# Mixer-Analog-OPA2134-Rev-K2.net
KiCad netlist of a schematic drawn in EAGLE
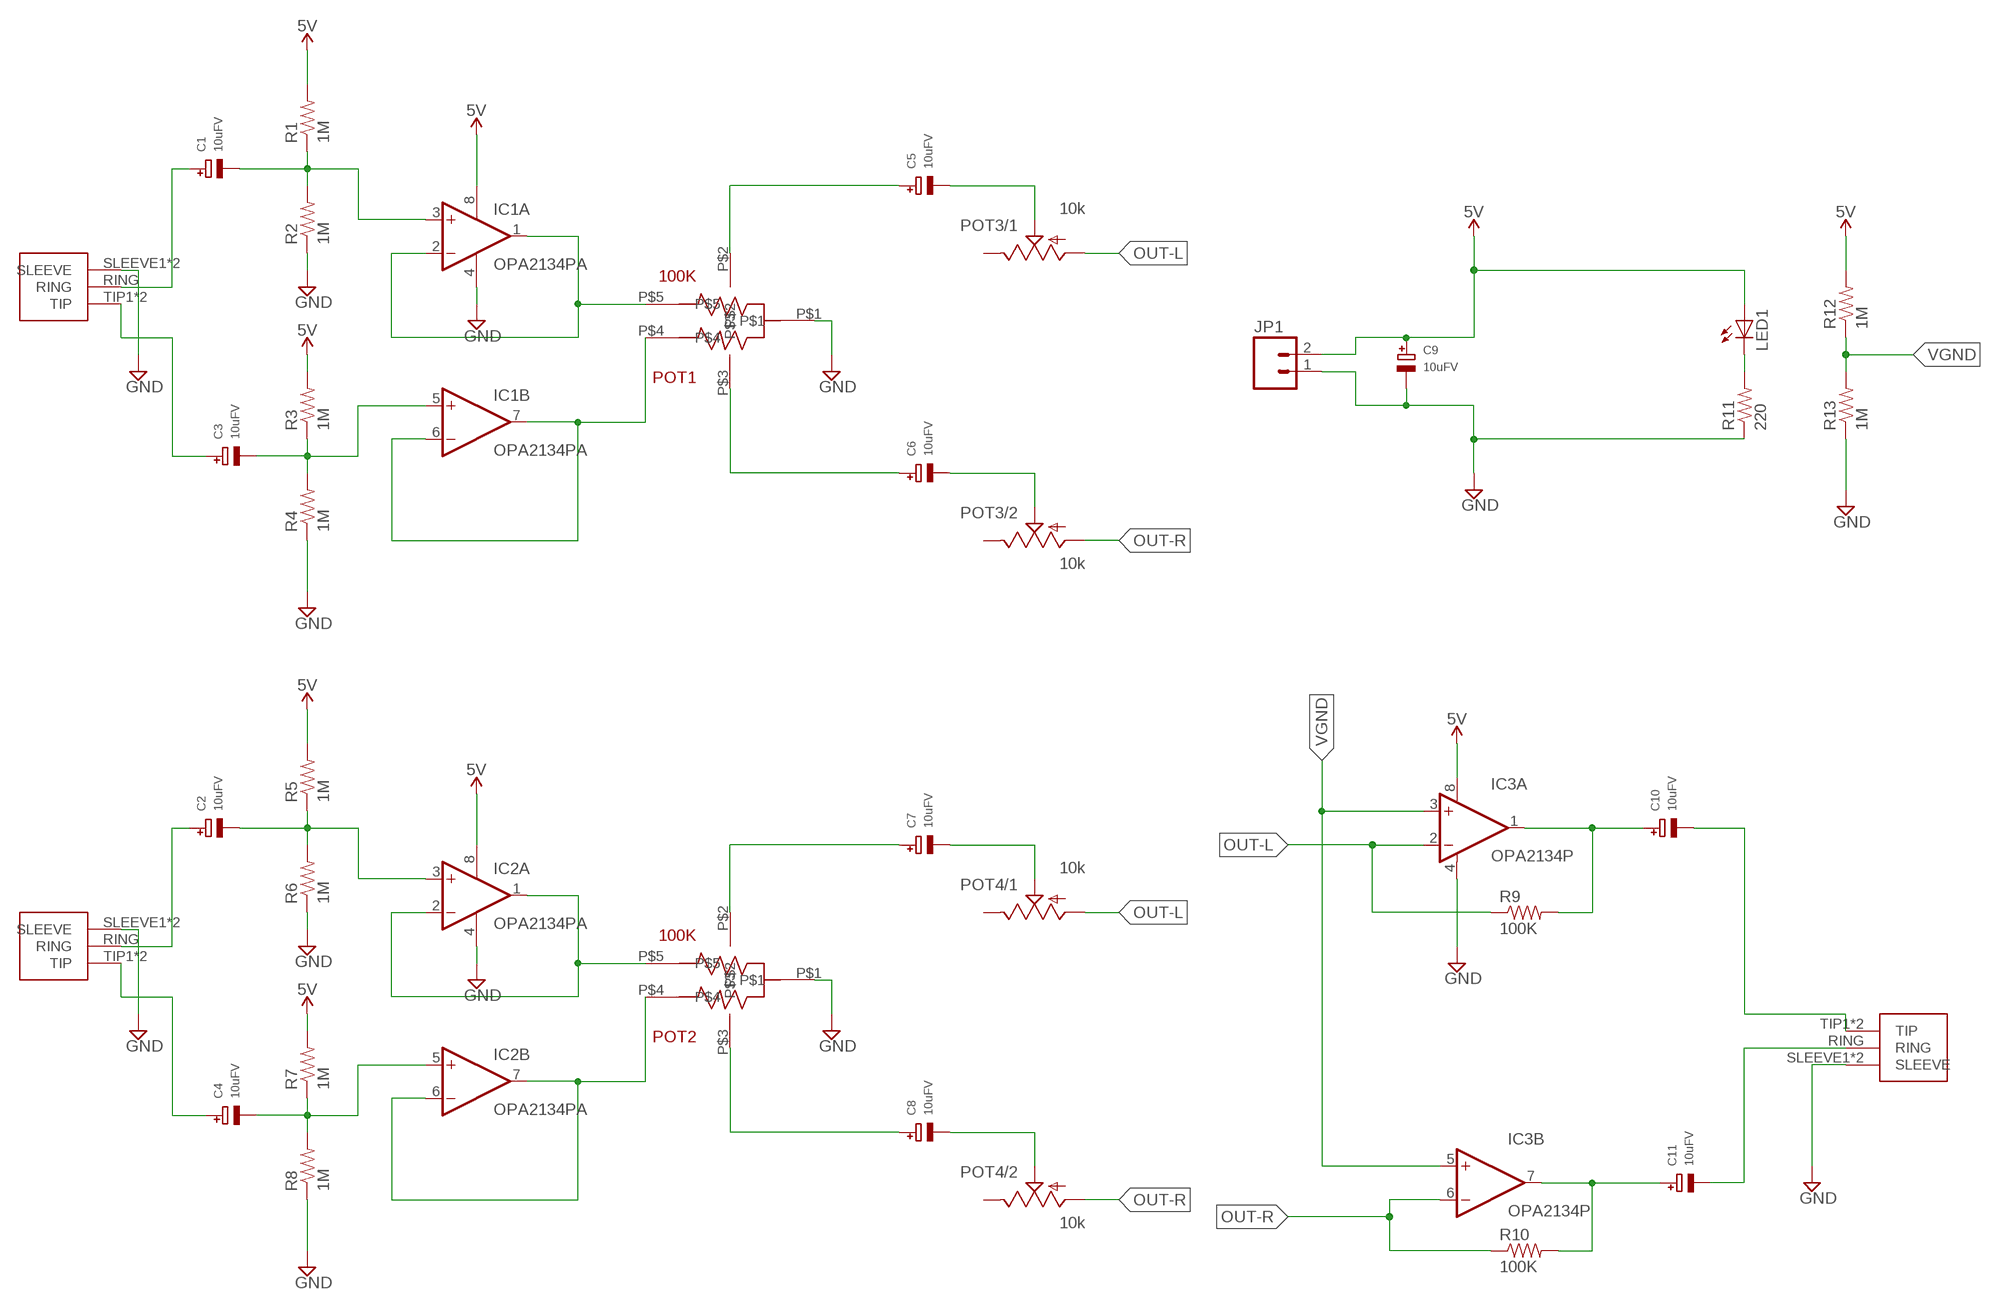
[diagram p0: schematic, sheet 1]

(export (version "E")
  (design (tool "Eeschema 10.0.6"))
  (components
    (comp (ref "C1")
      (value "10uFV")
      (footprint "eagle-import:CELEC_3.5MM_8MM")
      (libsource (lib "eagle-import") (part "CAP_ELECTROLYTICPTH_3.5MMGRID_8MMDIA"))
    )
    (comp (ref "C2")
      (value "10uFV")
      (footprint "eagle-import:CELEC_3.5MM_8MM")
      (libsource (lib "eagle-import") (part "CAP_ELECTROLYTICPTH_3.5MMGRID_8MMDIA"))
    )
    (comp (ref "C3")
      (value "10uFV")
      (footprint "eagle-import:CELEC_3.5MM_8MM")
      (libsource (lib "eagle-import") (part "CAP_ELECTROLYTICPTH_3.5MMGRID_8MMDIA"))
    )
    (comp (ref "C4")
      (value "10uFV")
      (footprint "eagle-import:CELEC_3.5MM_8MM")
      (libsource (lib "eagle-import") (part "CAP_ELECTROLYTICPTH_3.5MMGRID_8MMDIA"))
    )
    (comp (ref "C5")
      (value "10uFV")
      (footprint "eagle-import:CELEC_3.5MM_8MM")
      (libsource (lib "eagle-import") (part "CAP_ELECTROLYTICPTH_3.5MMGRID_8MMDIA"))
    )
    (comp (ref "C6")
      (value "10uFV")
      (footprint "eagle-import:CELEC_3.5MM_8MM")
      (libsource (lib "eagle-import") (part "CAP_ELECTROLYTICPTH_3.5MMGRID_8MMDIA"))
    )
    (comp (ref "C7")
      (value "10uFV")
      (footprint "eagle-import:CELEC_3.5MM_8MM")
      (libsource (lib "eagle-import") (part "CAP_ELECTROLYTICPTH_3.5MMGRID_8MMDIA"))
    )
    (comp (ref "C8")
      (value "10uFV")
      (footprint "eagle-import:CELEC_3.5MM_8MM")
      (libsource (lib "eagle-import") (part "CAP_ELECTROLYTICPTH_3.5MMGRID_8MMDIA"))
    )
    (comp (ref "C9")
      (value "10uFV")
      (footprint "eagle-import:CELEC_3.5MM_8MM")
      (libsource (lib "eagle-import") (part "CAP_ELECTROLYTICPTH_3.5MMGRID_8MMDIA"))
    )
    (comp (ref "C10")
      (value "10uFV")
      (footprint "eagle-import:CELEC_3.5MM_8MM")
      (libsource (lib "eagle-import") (part "CAP_ELECTROLYTICPTH_3.5MMGRID_8MMDIA"))
    )
    (comp (ref "C11")
      (value "10uFV")
      (footprint "eagle-import:CELEC_3.5MM_8MM")
      (libsource (lib "eagle-import") (part "CAP_ELECTROLYTICPTH_3.5MMGRID_8MMDIA"))
    )
    (comp (ref "IC1")
      (value "OPA2134PA")
      (footprint "eagle-import:DIL08")
      (libsource (lib "eagle-import") (part "OPA2PA134"))
    )
    (comp (ref "IC2")
      (value "OPA2134PA")
      (footprint "eagle-import:DIL08")
      (libsource (lib "eagle-import") (part "OPA2PA134"))
    )
    (comp (ref "IC3")
      (value "OPA2134P")
      (footprint "eagle-import:DIL08")
      (fields (field (name "MF") "TEXAS INSTRUMENTS") (field (name "MPN") "OPA2134PA"))
      (libsource (lib "eagle-import") (part "OPA2134P"))
    )
    (comp (ref "J1")
      (value "1/8\"-F-STEREO-PCB")
      (footprint "eagle-import:1_8_-F-STEREO-PCB")
      (libsource (lib "eagle-import") (part "1/8{dblquote}-F-STEREO-PCB"))
    )
    (comp (ref "J2")
      (value "1/8\"-F-STEREO-PCB")
      (footprint "eagle-import:1_8_-F-STEREO-PCB")
      (libsource (lib "eagle-import") (part "1/8{dblquote}-F-STEREO-PCB"))
    )
    (comp (ref "J3")
      (value "1/8\"-F-STEREO-PCB")
      (footprint "eagle-import:1_8_-F-STEREO-PCB")
      (libsource (lib "eagle-import") (part "1/8{dblquote}-F-STEREO-PCB"))
    )
    (comp (ref "JP1")
      (value "M02LOCK")
      (footprint "eagle-import:1X02_LOCK")
      (libsource (lib "eagle-import") (part "M02LOCK"))
    )
    (comp (ref "LED1")
      (value "LED3MM")
      (footprint "eagle-import:LED3MM")
      (libsource (lib "eagle-import") (part "LED3MM"))
    )
    (comp (ref "POT1")
      (value "100K")
      (footprint "eagle-import:POT-DUAL-ALPS-RK10J12E0A0A")
      (libsource (lib "eagle-import") (part "POT-DUAL-ALPS-RK10J12E0A0A"))
    )
    (comp (ref "POT2")
      (value "100K")
      (footprint "eagle-import:POT-DUAL-ALPS-RK10J12E0A0A")
      (libsource (lib "eagle-import") (part "POT-DUAL-ALPS-RK10J12E0A0A"))
    )
    (comp (ref "POT3")
      (value "10k")
      (footprint "eagle-import:PTV112")
      (fields
        (field (name "MF") "STMicroelectronics")
        (field (name "MP") "PTV112")
        (field (name "SPICEPREFIX") "J")
      )
      (libsource (lib "eagle-import") (part "POT-DUAL-PTV112-4420"))
    )
    (comp (ref "POT4")
      (value "10k")
      (footprint "eagle-import:PTV112")
      (fields
        (field (name "MF") "STMicroelectronics")
        (field (name "MP") "PTV112")
        (field (name "SPICEPREFIX") "J")
      )
      (libsource (lib "eagle-import") (part "POT-DUAL-PTV112-4420"))
    )
    (comp (ref "R1")
      (value "1M")
      (footprint "eagle-import:AXIAL-0.3EZ")
      (fields (field (name "SPICEPREFIX") "R"))
      (libsource (lib "eagle-import") (part "RESISTOREZ"))
    )
    (comp (ref "R2")
      (value "1M")
      (footprint "eagle-import:AXIAL-0.3")
      (fields (field (name "SPICEPREFIX") "R"))
      (libsource (lib "eagle-import") (part "RESISTORAXIAL-0.3"))
    )
    (comp (ref "R3")
      (value "1M")
      (footprint "eagle-import:AXIAL-0.3EZ")
      (fields (field (name "SPICEPREFIX") "R"))
      (libsource (lib "eagle-import") (part "RESISTOREZ"))
    )
    (comp (ref "R4")
      (value "1M")
      (footprint "eagle-import:AXIAL-0.3EZ")
      (fields (field (name "SPICEPREFIX") "R"))
      (libsource (lib "eagle-import") (part "RESISTOREZ"))
    )
    (comp (ref "R5")
      (value "1M")
      (footprint "eagle-import:AXIAL-0.3EZ")
      (fields (field (name "SPICEPREFIX") "R"))
      (libsource (lib "eagle-import") (part "RESISTOREZ"))
    )
    (comp (ref "R6")
      (value "1M")
      (footprint "eagle-import:AXIAL-0.3")
      (fields (field (name "SPICEPREFIX") "R"))
      (libsource (lib "eagle-import") (part "RESISTORAXIAL-0.3"))
    )
    (comp (ref "R7")
      (value "1M")
      (footprint "eagle-import:AXIAL-0.3EZ")
      (fields (field (name "SPICEPREFIX") "R"))
      (libsource (lib "eagle-import") (part "RESISTOREZ"))
    )
    (comp (ref "R8")
      (value "1M")
      (footprint "eagle-import:AXIAL-0.3EZ")
      (fields (field (name "SPICEPREFIX") "R"))
      (libsource (lib "eagle-import") (part "RESISTOREZ"))
    )
    (comp (ref "R9")
      (value "100K")
      (footprint "eagle-import:AXIAL-0.3EZ")
      (fields (field (name "SPICEPREFIX") "R"))
      (libsource (lib "eagle-import") (part "RESISTOREZ"))
    )
    (comp (ref "R10")
      (value "100K")
      (footprint "eagle-import:AXIAL-0.3EZ")
      (fields (field (name "SPICEPREFIX") "R"))
      (libsource (lib "eagle-import") (part "RESISTOREZ"))
    )
    (comp (ref "R11")
      (value "220")
      (footprint "eagle-import:AXIAL-0.3EZ")
      (libsource (lib "eagle-import") (part "RESISTOREZ"))
    )
    (comp (ref "R12")
      (value "1M")
      (footprint "eagle-import:AXIAL-0.3EZ")
      (libsource (lib "eagle-import") (part "RESISTOREZ"))
    )
    (comp (ref "R13")
      (value "1M")
      (footprint "eagle-import:AXIAL-0.3EZ")
      (libsource (lib "eagle-import") (part "RESISTOREZ"))
    )
  )
  (nets
    (net (code "1") (name "5V") (class "Default")
      (node (ref "C9") (pin "+") (pinfunction "+_+") (pintype "passive"))
      (node (ref "IC1") (pin "8") (pinfunction "V+_8") (pintype "power_in"))
      (node (ref "IC2") (pin "8") (pinfunction "V+_8") (pintype "power_in"))
      (node (ref "IC3") (pin "8") (pinfunction "V+_8") (pintype "power_in"))
      (node (ref "JP1") (pin "2") (pinfunction "2_2") (pintype "passive"))
      (node (ref "LED1") (pin "A") (pinfunction "A_A") (pintype "passive"))
      (node (ref "R1") (pin "P$2") (pinfunction "2_P$2") (pintype "passive"))
      (node (ref "R12") (pin "P$2") (pinfunction "2_P$2") (pintype "passive"))
      (node (ref "R3") (pin "P$2") (pinfunction "2_P$2") (pintype "passive"))
      (node (ref "R5") (pin "P$2") (pinfunction "2_P$2") (pintype "passive"))
      (node (ref "R7") (pin "P$2") (pinfunction "2_P$2") (pintype "passive"))
    )
    (net (code "2") (name "GND") (class "Default")
      (node (ref "C9") (pin "-") (pinfunction "-_-") (pintype "passive"))
      (node (ref "IC1") (pin "4") (pinfunction "V-_4") (pintype "power_in"))
      (node (ref "IC2") (pin "4") (pinfunction "V-_4") (pintype "power_in"))
      (node (ref "IC3") (pin "4") (pinfunction "V-_4") (pintype "power_in"))
      (node (ref "J1") (pin "SLEEVE1") (pinfunction "SLEEVE_SLEEVE1") (pintype "bidirectional"))
      (node (ref "J1") (pin "SLEEVE2") (pinfunction "SLEEVE_SLEEVE2") (pintype "bidirectional"))
      (node (ref "J2") (pin "SLEEVE1") (pinfunction "SLEEVE_SLEEVE1") (pintype "bidirectional"))
      (node (ref "J2") (pin "SLEEVE2") (pinfunction "SLEEVE_SLEEVE2") (pintype "bidirectional"))
      (node (ref "J3") (pin "SLEEVE1") (pinfunction "SLEEVE_SLEEVE1") (pintype "bidirectional"))
      (node (ref "J3") (pin "SLEEVE2") (pinfunction "SLEEVE_SLEEVE2") (pintype "bidirectional"))
      (node (ref "JP1") (pin "1") (pinfunction "1_1") (pintype "passive"))
      (node (ref "POT1") (pin "P$1") (pinfunction "P$1_P$1") (pintype "bidirectional"))
      (node (ref "POT2") (pin "P$1") (pinfunction "P$1_P$1") (pintype "bidirectional"))
      (node (ref "R11") (pin "P$1") (pinfunction "1_P$1") (pintype "passive"))
      (node (ref "R13") (pin "P$1") (pinfunction "1_P$1") (pintype "passive"))
      (node (ref "R2") (pin "P$1") (pinfunction "1_P$1") (pintype "passive"))
      (node (ref "R4") (pin "P$1") (pinfunction "1_P$1") (pintype "passive"))
      (node (ref "R6") (pin "P$1") (pinfunction "1_P$1") (pintype "passive"))
      (node (ref "R8") (pin "P$1") (pinfunction "1_P$1") (pintype "passive"))
    )
    (net (code "3") (name "Net-(C1-Pad+)") (class "Default")
      (node (ref "C1") (pin "+") (pinfunction "+_+") (pintype "passive"))
      (node (ref "J1") (pin "RING") (pinfunction "RING_RING") (pintype "bidirectional"))
    )
    (net (code "4") (name "Net-(C2-Pad+)") (class "Default")
      (node (ref "C2") (pin "+") (pinfunction "+_+") (pintype "passive"))
      (node (ref "J2") (pin "RING") (pinfunction "RING_RING") (pintype "bidirectional"))
    )
    (net (code "5") (name "Net-(C3-Pad+)") (class "Default")
      (node (ref "C3") (pin "+") (pinfunction "+_+") (pintype "passive"))
      (node (ref "J1") (pin "TIP1") (pinfunction "TIP_TIP1") (pintype "bidirectional"))
      (node (ref "J1") (pin "TIP2") (pinfunction "TIP_TIP2") (pintype "bidirectional"))
    )
    (net (code "6") (name "Net-(C4-Pad+)") (class "Default")
      (node (ref "C4") (pin "+") (pinfunction "+_+") (pintype "passive"))
      (node (ref "J2") (pin "TIP1") (pinfunction "TIP_TIP1") (pintype "bidirectional"))
      (node (ref "J2") (pin "TIP2") (pinfunction "TIP_TIP2") (pintype "bidirectional"))
    )
    (net (code "7") (name "Net-(C5-Pad+)") (class "Default")
      (node (ref "C5") (pin "+") (pinfunction "+_+") (pintype "passive"))
      (node (ref "POT1") (pin "P$2") (pinfunction "P$2_P$2") (pintype "bidirectional"))
    )
    (net (code "8") (name "Net-(C6-Pad+)") (class "Default")
      (node (ref "C6") (pin "+") (pinfunction "+_+") (pintype "passive"))
      (node (ref "POT1") (pin "P$3") (pinfunction "P$3_P$3") (pintype "bidirectional"))
    )
    (net (code "9") (name "Net-(C7-Pad+)") (class "Default")
      (node (ref "C7") (pin "+") (pinfunction "+_+") (pintype "passive"))
      (node (ref "POT2") (pin "P$2") (pinfunction "P$2_P$2") (pintype "bidirectional"))
    )
    (net (code "10") (name "Net-(C8-Pad+)") (class "Default")
      (node (ref "C8") (pin "+") (pinfunction "+_+") (pintype "passive"))
      (node (ref "POT2") (pin "P$3") (pinfunction "P$3_P$3") (pintype "bidirectional"))
    )
    (net (code "11") (name "Net-(C10-Pad-)") (class "Default")
      (node (ref "C10") (pin "-") (pinfunction "-_-") (pintype "passive"))
      (node (ref "J3") (pin "TIP1") (pinfunction "TIP_TIP1") (pintype "bidirectional"))
      (node (ref "J3") (pin "TIP2") (pinfunction "TIP_TIP2") (pintype "bidirectional"))
    )
    (net (code "12") (name "Net-(C11-Pad-)") (class "Default")
      (node (ref "C11") (pin "-") (pinfunction "-_-") (pintype "passive"))
      (node (ref "J3") (pin "RING") (pinfunction "RING_RING") (pintype "bidirectional"))
    )
    (net (code "13") (name "Net-(IC1A-+IN)") (class "Default")
      (node (ref "C1") (pin "-") (pinfunction "-_-") (pintype "passive"))
      (node (ref "IC1") (pin "3") (pinfunction "+IN_3") (pintype "input"))
      (node (ref "R1") (pin "P$1") (pinfunction "1_P$1") (pintype "passive"))
      (node (ref "R2") (pin "P$2") (pinfunction "2_P$2") (pintype "passive"))
    )
    (net (code "14") (name "Net-(IC1A--IN)") (class "Default")
      (node (ref "IC1") (pin "1") (pinfunction "OUT_1") (pintype "output"))
      (node (ref "IC1") (pin "2") (pinfunction "-IN_2") (pintype "input"))
      (node (ref "POT1") (pin "P$5") (pinfunction "P$5_P$5") (pintype "bidirectional"))
    )
    (net (code "15") (name "Net-(IC1B-+IN)") (class "Default")
      (node (ref "C3") (pin "-") (pinfunction "-_-") (pintype "passive"))
      (node (ref "IC1") (pin "5") (pinfunction "+IN_5") (pintype "input"))
      (node (ref "R3") (pin "P$1") (pinfunction "1_P$1") (pintype "passive"))
      (node (ref "R4") (pin "P$2") (pinfunction "2_P$2") (pintype "passive"))
    )
    (net (code "16") (name "Net-(IC1B--IN)") (class "Default")
      (node (ref "IC1") (pin "6") (pinfunction "-IN_6") (pintype "input"))
      (node (ref "IC1") (pin "7") (pinfunction "OUT_7") (pintype "output"))
      (node (ref "POT1") (pin "P$4") (pinfunction "P$4_P$4") (pintype "bidirectional"))
    )
    (net (code "17") (name "Net-(IC2A-+IN)") (class "Default")
      (node (ref "C2") (pin "-") (pinfunction "-_-") (pintype "passive"))
      (node (ref "IC2") (pin "3") (pinfunction "+IN_3") (pintype "input"))
      (node (ref "R5") (pin "P$1") (pinfunction "1_P$1") (pintype "passive"))
      (node (ref "R6") (pin "P$2") (pinfunction "2_P$2") (pintype "passive"))
    )
    (net (code "18") (name "Net-(IC2A--IN)") (class "Default")
      (node (ref "IC2") (pin "1") (pinfunction "OUT_1") (pintype "output"))
      (node (ref "IC2") (pin "2") (pinfunction "-IN_2") (pintype "input"))
      (node (ref "POT2") (pin "P$5") (pinfunction "P$5_P$5") (pintype "bidirectional"))
    )
    (net (code "19") (name "Net-(IC2B-+IN)") (class "Default")
      (node (ref "C4") (pin "-") (pinfunction "-_-") (pintype "passive"))
      (node (ref "IC2") (pin "5") (pinfunction "+IN_5") (pintype "input"))
      (node (ref "R7") (pin "P$1") (pinfunction "1_P$1") (pintype "passive"))
      (node (ref "R8") (pin "P$2") (pinfunction "2_P$2") (pintype "passive"))
    )
    (net (code "20") (name "Net-(IC2B--IN)") (class "Default")
      (node (ref "IC2") (pin "6") (pinfunction "-IN_6") (pintype "input"))
      (node (ref "IC2") (pin "7") (pinfunction "OUT_7") (pintype "output"))
      (node (ref "POT2") (pin "P$4") (pinfunction "P$4_P$4") (pintype "bidirectional"))
    )
    (net (code "21") (name "Net-(IC3A-OUT)") (class "Default")
      (node (ref "C10") (pin "+") (pinfunction "+_+") (pintype "passive"))
      (node (ref "IC3") (pin "1") (pinfunction "OUT_1") (pintype "output"))
      (node (ref "R9") (pin "P$2") (pinfunction "2_P$2") (pintype "passive"))
    )
    (net (code "22") (name "Net-(IC3B-OUT)") (class "Default")
      (node (ref "C11") (pin "+") (pinfunction "+_+") (pintype "passive"))
      (node (ref "IC3") (pin "7") (pinfunction "OUT_7") (pintype "output"))
      (node (ref "R10") (pin "P$2") (pinfunction "2_P$2") (pintype "passive"))
    )
    (net (code "23") (name "Net-(LED1-C)") (class "Default")
      (node (ref "LED1") (pin "K") (pinfunction "C_K") (pintype "passive"))
      (node (ref "R11") (pin "P$2") (pinfunction "2_P$2") (pintype "passive"))
    )
    (net (code "24") (name "Net-(POT3A-S)") (class "Default")
      (node (ref "C5") (pin "-") (pinfunction "-_-") (pintype "passive"))
      (node (ref "POT3") (pin "1.2") (pinfunction "S_1.2") (pintype "passive"))
    )
    (net (code "25") (name "Net-(POT3B-S)") (class "Default")
      (node (ref "C6") (pin "-") (pinfunction "-_-") (pintype "passive"))
      (node (ref "POT3") (pin "2.2") (pinfunction "S_2.2") (pintype "passive"))
    )
    (net (code "26") (name "Net-(POT4A-S)") (class "Default")
      (node (ref "C7") (pin "-") (pinfunction "-_-") (pintype "passive"))
      (node (ref "POT4") (pin "1.2") (pinfunction "S_1.2") (pintype "passive"))
    )
    (net (code "27") (name "Net-(POT4B-S)") (class "Default")
      (node (ref "C8") (pin "-") (pinfunction "-_-") (pintype "passive"))
      (node (ref "POT4") (pin "2.2") (pinfunction "S_2.2") (pintype "passive"))
    )
    (net (code "28") (name "OUT-L") (class "Default")
      (node (ref "IC3") (pin "2") (pinfunction "-IN_2") (pintype "input"))
      (node (ref "POT3") (pin "1.1") (pinfunction "A_1.1") (pintype "passive"))
      (node (ref "POT4") (pin "1.1") (pinfunction "A_1.1") (pintype "passive"))
      (node (ref "R9") (pin "P$1") (pinfunction "1_P$1") (pintype "passive"))
    )
    (net (code "29") (name "OUT-R") (class "Default")
      (node (ref "IC3") (pin "6") (pinfunction "-IN_6") (pintype "input"))
      (node (ref "POT3") (pin "2.1") (pinfunction "A_2.1") (pintype "passive"))
      (node (ref "POT4") (pin "2.1") (pinfunction "A_2.1") (pintype "passive"))
      (node (ref "R10") (pin "P$1") (pinfunction "1_P$1") (pintype "passive"))
    )
    (net (code "30") (name "VGND") (class "Default")
      (node (ref "IC3") (pin "3") (pinfunction "+IN_3") (pintype "input"))
      (node (ref "IC3") (pin "5") (pinfunction "+IN_5") (pintype "input"))
      (node (ref "R12") (pin "P$1") (pinfunction "1_P$1") (pintype "passive"))
      (node (ref "R13") (pin "P$2") (pinfunction "2_P$2") (pintype "passive"))
    )
    (net (code "31") (name "unconnected-(POT3A-E-Pad1.3)") (class "Default")
      (node (ref "POT3") (pin "1.3") (pinfunction "E_1.3") (pintype "passive"))
    )
    (net (code "32") (name "unconnected-(POT3B-E-Pad2.3)") (class "Default")
      (node (ref "POT3") (pin "2.3") (pinfunction "E_2.3") (pintype "passive"))
    )
    (net (code "33") (name "unconnected-(POT4A-E-Pad1.3)") (class "Default")
      (node (ref "POT4") (pin "1.3") (pinfunction "E_1.3") (pintype "passive"))
    )
    (net (code "34") (name "unconnected-(POT4B-E-Pad2.3)") (class "Default")
      (node (ref "POT4") (pin "2.3") (pinfunction "E_2.3") (pintype "passive"))
    )
  )
)
